# testbrd.net
KiCad netlist of a schematic drawn in EAGLE
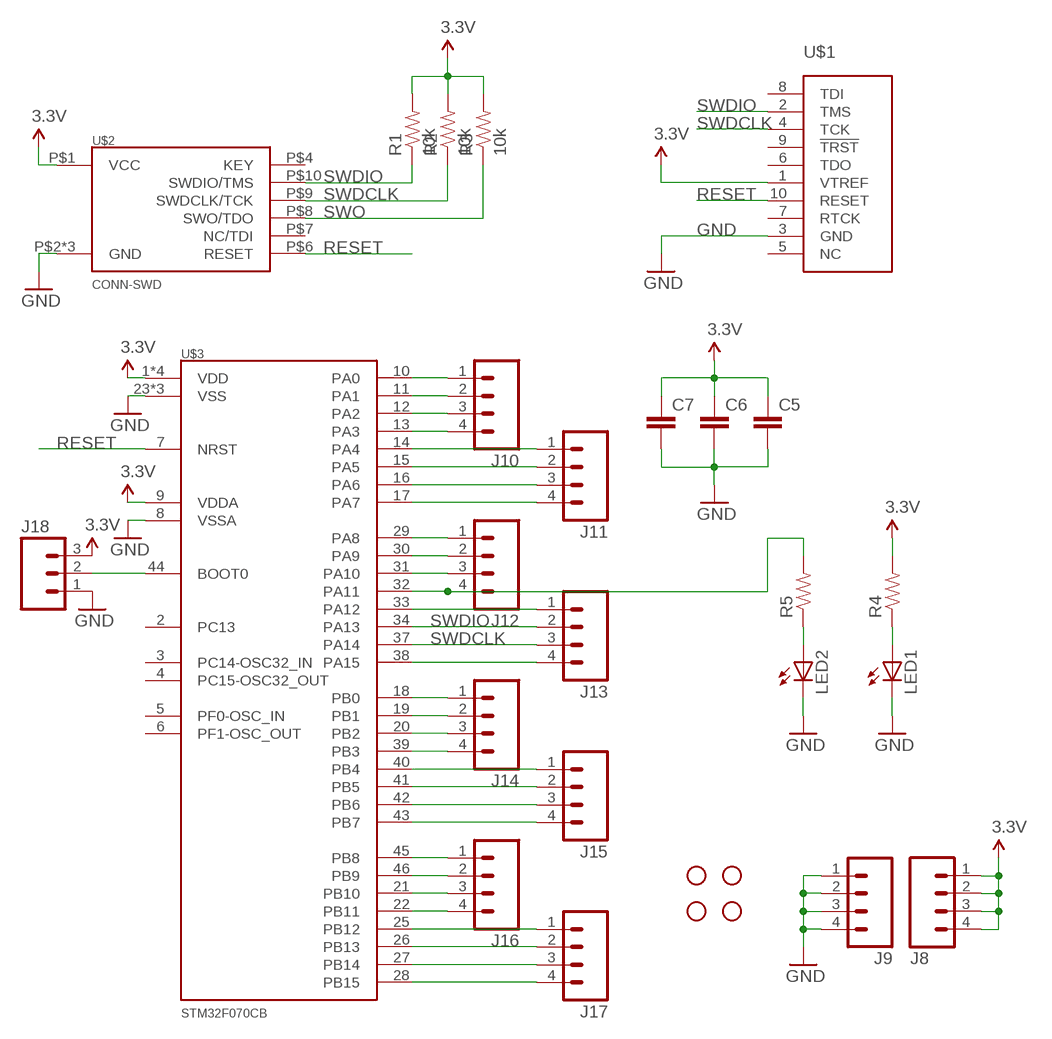
[diagram p0: schematic, sheet 1]

(export (version "E")
  (design (tool "Eeschema 10.0.6"))
  (components
    (comp (ref "C5")
      (value "CAP0805")
      (footprint "eagle-import:0805")
      (libsource (lib "eagle-import") (part "CAP0805"))
    )
    (comp (ref "C6")
      (value "CAP0805")
      (footprint "eagle-import:0805")
      (libsource (lib "eagle-import") (part "CAP0805"))
    )
    (comp (ref "C7")
      (value "CAP0805")
      (footprint "eagle-import:0805")
      (libsource (lib "eagle-import") (part "CAP0805"))
    )
    (comp (ref "H1")
      (value "STAND-OFF")
      (footprint "eagle-import:STAND-OFF")
      (libsource (lib "eagle-import") (part "STAND-OFF"))
    )
    (comp (ref "H2")
      (value "STAND-OFF")
      (footprint "eagle-import:STAND-OFF")
      (libsource (lib "eagle-import") (part "STAND-OFF"))
    )
    (comp (ref "H3")
      (value "STAND-OFF")
      (footprint "eagle-import:STAND-OFF")
      (libsource (lib "eagle-import") (part "STAND-OFF"))
    )
    (comp (ref "H4")
      (value "STAND-OFF")
      (footprint "eagle-import:STAND-OFF")
      (libsource (lib "eagle-import") (part "STAND-OFF"))
    )
    (comp (ref "J8")
      (value "M04PTH")
      (footprint "eagle-import:1X04")
      (libsource (lib "eagle-import") (part "M04PTH"))
    )
    (comp (ref "J9")
      (value "M04PTH")
      (footprint "eagle-import:1X04")
      (libsource (lib "eagle-import") (part "M04PTH"))
    )
    (comp (ref "J10")
      (value "M04PTH")
      (footprint "eagle-import:1X04")
      (libsource (lib "eagle-import") (part "M04PTH"))
    )
    (comp (ref "J11")
      (value "M04PTH")
      (footprint "eagle-import:1X04")
      (libsource (lib "eagle-import") (part "M04PTH"))
    )
    (comp (ref "J12")
      (value "M04PTH")
      (footprint "eagle-import:1X04")
      (libsource (lib "eagle-import") (part "M04PTH"))
    )
    (comp (ref "J13")
      (value "M04PTH")
      (footprint "eagle-import:1X04")
      (libsource (lib "eagle-import") (part "M04PTH"))
    )
    (comp (ref "J14")
      (value "M04PTH")
      (footprint "eagle-import:1X04")
      (libsource (lib "eagle-import") (part "M04PTH"))
    )
    (comp (ref "J15")
      (value "M04PTH")
      (footprint "eagle-import:1X04")
      (libsource (lib "eagle-import") (part "M04PTH"))
    )
    (comp (ref "J16")
      (value "M04PTH")
      (footprint "eagle-import:1X04")
      (libsource (lib "eagle-import") (part "M04PTH"))
    )
    (comp (ref "J17")
      (value "M04PTH")
      (footprint "eagle-import:1X04")
      (libsource (lib "eagle-import") (part "M04PTH"))
    )
    (comp (ref "J18")
      (value "M03PTH")
      (footprint "eagle-import:1X03")
      (libsource (lib "eagle-import") (part "M03PTH"))
    )
    (comp (ref "LED1")
      (value "LEDCHIPLED_0805")
      (footprint "eagle-import:CHIPLED_0805")
      (libsource (lib "eagle-import") (part "LEDCHIPLED_0805"))
    )
    (comp (ref "LED2")
      (value "LEDCHIPLED_0805")
      (footprint "eagle-import:CHIPLED_0805")
      (libsource (lib "eagle-import") (part "LEDCHIPLED_0805"))
    )
    (comp (ref "R1")
      (value "10k")
      (footprint "eagle-import:0805")
      (libsource (lib "eagle-import") (part "RESISTOR0805-RES"))
    )
    (comp (ref "R2")
      (value "10k")
      (footprint "eagle-import:0805")
      (libsource (lib "eagle-import") (part "RESISTOR0805-RES"))
    )
    (comp (ref "R3")
      (value "10k")
      (footprint "eagle-import:0805")
      (libsource (lib "eagle-import") (part "RESISTOR0805-RES"))
    )
    (comp (ref "R4")
      (value "RESISTOR0805-RES")
      (footprint "eagle-import:0805")
      (libsource (lib "eagle-import") (part "RESISTOR0805-RES"))
    )
    (comp (ref "R5")
      (value "RESISTOR0805-RES")
      (footprint "eagle-import:0805")
      (libsource (lib "eagle-import") (part "RESISTOR0805-RES"))
    )
    (comp (ref "U$1")
      (value "TC2050-MCP-NL")
      (footprint "eagle-import:TC2050")
      (libsource (lib "eagle-import") (part "TC2050-MCP-NL"))
    )
    (comp (ref "U$2")
      (value "CONN-SWD")
      (footprint "eagle-import:CONN2X5")
      (libsource (lib "eagle-import") (part "CONN-SWD"))
    )
    (comp (ref "U$3")
      (value "STM32F070CB")
      (footprint "eagle-import:LQFP-48")
      (libsource (lib "eagle-import") (part "STM32F070CB"))
    )
  )
  (nets
    (net (code "1") (name "/RESET") (class "Default")
      (node (ref "U$1") (pin "10") (pinfunction "RESET_10") (pintype "bidirectional"))
      (node (ref "U$2") (pin "P$6") (pinfunction "RESET_P$6") (pintype "bidirectional"))
      (node (ref "U$3") (pin "7") (pinfunction "NRST_7") (pintype "bidirectional"))
    )
    (net (code "2") (name "/SWDCLK") (class "Default")
      (node (ref "J13") (pin "3") (pinfunction "3_3") (pintype "passive"))
      (node (ref "R2") (pin "1") (pinfunction "1_1") (pintype "passive"))
      (node (ref "U$1") (pin "4") (pinfunction "TCK_4") (pintype "bidirectional"))
      (node (ref "U$2") (pin "P$9") (pinfunction "SWDCLK/TCK_P$9") (pintype "bidirectional"))
      (node (ref "U$3") (pin "37") (pinfunction "PA14_37") (pintype "bidirectional"))
    )
    (net (code "3") (name "/SWDIO") (class "Default")
      (node (ref "J13") (pin "2") (pinfunction "2_2") (pintype "passive"))
      (node (ref "R1") (pin "1") (pinfunction "1_1") (pintype "passive"))
      (node (ref "U$1") (pin "2") (pinfunction "TMS_2") (pintype "bidirectional"))
      (node (ref "U$2") (pin "P$10") (pinfunction "SWDIO/TMS_P$10") (pintype "bidirectional"))
      (node (ref "U$3") (pin "34") (pinfunction "PA13_34") (pintype "bidirectional"))
    )
    (net (code "4") (name "/SWO") (class "Default")
      (node (ref "R3") (pin "1") (pinfunction "1_1") (pintype "passive"))
      (node (ref "U$2") (pin "P$8") (pinfunction "SWO/TDO_P$8") (pintype "bidirectional"))
    )
    (net (code "5") (name "3.3V") (class "Default")
      (node (ref "C5") (pin "1") (pinfunction "1_1") (pintype "passive"))
      (node (ref "C6") (pin "1") (pinfunction "1_1") (pintype "passive"))
      (node (ref "C7") (pin "1") (pinfunction "1_1") (pintype "passive"))
      (node (ref "J18") (pin "3") (pinfunction "3_3") (pintype "passive"))
      (node (ref "J8") (pin "1") (pinfunction "1_1") (pintype "passive"))
      (node (ref "J8") (pin "2") (pinfunction "2_2") (pintype "passive"))
      (node (ref "J8") (pin "3") (pinfunction "3_3") (pintype "passive"))
      (node (ref "J8") (pin "4") (pinfunction "4_4") (pintype "passive"))
      (node (ref "R1") (pin "2") (pinfunction "2_2") (pintype "passive"))
      (node (ref "R2") (pin "2") (pinfunction "2_2") (pintype "passive"))
      (node (ref "R3") (pin "2") (pinfunction "2_2") (pintype "passive"))
      (node (ref "R4") (pin "2") (pinfunction "2_2") (pintype "passive"))
      (node (ref "U$1") (pin "1") (pinfunction "VTREF_1") (pintype "bidirectional"))
      (node (ref "U$2") (pin "P$1") (pinfunction "VCC_P$1") (pintype "bidirectional"))
      (node (ref "U$3") (pin "1") (pinfunction "VDD_1") (pintype "bidirectional"))
      (node (ref "U$3") (pin "24") (pinfunction "VDD_24") (pintype "bidirectional"))
      (node (ref "U$3") (pin "36") (pinfunction "VDD_36") (pintype "bidirectional"))
      (node (ref "U$3") (pin "48") (pinfunction "VDD_48") (pintype "bidirectional"))
      (node (ref "U$3") (pin "9") (pinfunction "VDDA_9") (pintype "bidirectional"))
    )
    (net (code "6") (name "GND") (class "Default")
      (node (ref "C5") (pin "2") (pinfunction "2_2") (pintype "passive"))
      (node (ref "C6") (pin "2") (pinfunction "2_2") (pintype "passive"))
      (node (ref "C7") (pin "2") (pinfunction "2_2") (pintype "passive"))
      (node (ref "J18") (pin "1") (pinfunction "1_1") (pintype "passive"))
      (node (ref "J9") (pin "1") (pinfunction "1_1") (pintype "passive"))
      (node (ref "J9") (pin "2") (pinfunction "2_2") (pintype "passive"))
      (node (ref "J9") (pin "3") (pinfunction "3_3") (pintype "passive"))
      (node (ref "J9") (pin "4") (pinfunction "4_4") (pintype "passive"))
      (node (ref "LED1") (pin "C") (pinfunction "C_C") (pintype "passive"))
      (node (ref "LED2") (pin "C") (pinfunction "C_C") (pintype "passive"))
      (node (ref "U$1") (pin "3") (pinfunction "GND_3") (pintype "bidirectional"))
      (node (ref "U$2") (pin "P$2") (pinfunction "GND_P$2") (pintype "bidirectional"))
      (node (ref "U$2") (pin "P$3") (pinfunction "GND_P$3") (pintype "bidirectional"))
      (node (ref "U$2") (pin "P$5") (pinfunction "GND_P$5") (pintype "bidirectional"))
      (node (ref "U$3") (pin "23") (pinfunction "VSS_23") (pintype "bidirectional"))
      (node (ref "U$3") (pin "35") (pinfunction "VSS_35") (pintype "bidirectional"))
      (node (ref "U$3") (pin "47") (pinfunction "VSS_47") (pintype "bidirectional"))
      (node (ref "U$3") (pin "8") (pinfunction "VSSA_8") (pintype "bidirectional"))
    )
    (net (code "7") (name "Net-(LED1-PadA)") (class "Default")
      (node (ref "LED1") (pin "A") (pinfunction "A_A") (pintype "passive"))
      (node (ref "R4") (pin "1") (pinfunction "1_1") (pintype "passive"))
    )
    (net (code "8") (name "Net-(LED2-PadA)") (class "Default")
      (node (ref "LED2") (pin "A") (pinfunction "A_A") (pintype "passive"))
      (node (ref "R5") (pin "1") (pinfunction "1_1") (pintype "passive"))
    )
    (net (code "9") (name "Net-(U$3-BOOT0)") (class "Default")
      (node (ref "J18") (pin "2") (pinfunction "2_2") (pintype "passive"))
      (node (ref "U$3") (pin "44") (pinfunction "BOOT0_44") (pintype "bidirectional"))
    )
    (net (code "10") (name "Net-(U$3-PA0)") (class "Default")
      (node (ref "J10") (pin "1") (pinfunction "1_1") (pintype "passive"))
      (node (ref "U$3") (pin "10") (pinfunction "PA0_10") (pintype "bidirectional"))
    )
    (net (code "11") (name "Net-(U$3-PA1)") (class "Default")
      (node (ref "J10") (pin "2") (pinfunction "2_2") (pintype "passive"))
      (node (ref "U$3") (pin "11") (pinfunction "PA1_11") (pintype "bidirectional"))
    )
    (net (code "12") (name "Net-(U$3-PA2)") (class "Default")
      (node (ref "J10") (pin "3") (pinfunction "3_3") (pintype "passive"))
      (node (ref "U$3") (pin "12") (pinfunction "PA2_12") (pintype "bidirectional"))
    )
    (net (code "13") (name "Net-(U$3-PA3)") (class "Default")
      (node (ref "J10") (pin "4") (pinfunction "4_4") (pintype "passive"))
      (node (ref "U$3") (pin "13") (pinfunction "PA3_13") (pintype "bidirectional"))
    )
    (net (code "14") (name "Net-(U$3-PA4)") (class "Default")
      (node (ref "J11") (pin "1") (pinfunction "1_1") (pintype "passive"))
      (node (ref "U$3") (pin "14") (pinfunction "PA4_14") (pintype "bidirectional"))
    )
    (net (code "15") (name "Net-(U$3-PA5)") (class "Default")
      (node (ref "J11") (pin "2") (pinfunction "2_2") (pintype "passive"))
      (node (ref "U$3") (pin "15") (pinfunction "PA5_15") (pintype "bidirectional"))
    )
    (net (code "16") (name "Net-(U$3-PA6)") (class "Default")
      (node (ref "J11") (pin "3") (pinfunction "3_3") (pintype "passive"))
      (node (ref "U$3") (pin "16") (pinfunction "PA6_16") (pintype "bidirectional"))
    )
    (net (code "17") (name "Net-(U$3-PA7)") (class "Default")
      (node (ref "J11") (pin "4") (pinfunction "4_4") (pintype "passive"))
      (node (ref "U$3") (pin "17") (pinfunction "PA7_17") (pintype "bidirectional"))
    )
    (net (code "18") (name "Net-(U$3-PA8)") (class "Default")
      (node (ref "J12") (pin "1") (pinfunction "1_1") (pintype "passive"))
      (node (ref "U$3") (pin "29") (pinfunction "PA8_29") (pintype "bidirectional"))
    )
    (net (code "19") (name "Net-(U$3-PA9)") (class "Default")
      (node (ref "J12") (pin "2") (pinfunction "2_2") (pintype "passive"))
      (node (ref "U$3") (pin "30") (pinfunction "PA9_30") (pintype "bidirectional"))
    )
    (net (code "20") (name "Net-(U$3-PA10)") (class "Default")
      (node (ref "J12") (pin "3") (pinfunction "3_3") (pintype "passive"))
      (node (ref "U$3") (pin "31") (pinfunction "PA10_31") (pintype "bidirectional"))
    )
    (net (code "21") (name "Net-(U$3-PA11)") (class "Default")
      (node (ref "J12") (pin "4") (pinfunction "4_4") (pintype "passive"))
      (node (ref "R5") (pin "2") (pinfunction "2_2") (pintype "passive"))
      (node (ref "U$3") (pin "32") (pinfunction "PA11_32") (pintype "bidirectional"))
    )
    (net (code "22") (name "Net-(U$3-PA12)") (class "Default")
      (node (ref "J13") (pin "1") (pinfunction "1_1") (pintype "passive"))
      (node (ref "U$3") (pin "33") (pinfunction "PA12_33") (pintype "bidirectional"))
    )
    (net (code "23") (name "Net-(U$3-PA15)") (class "Default")
      (node (ref "J13") (pin "4") (pinfunction "4_4") (pintype "passive"))
      (node (ref "U$3") (pin "38") (pinfunction "PA15_38") (pintype "bidirectional"))
    )
    (net (code "24") (name "Net-(U$3-PB0)") (class "Default")
      (node (ref "J14") (pin "1") (pinfunction "1_1") (pintype "passive"))
      (node (ref "U$3") (pin "18") (pinfunction "PB0_18") (pintype "bidirectional"))
    )
    (net (code "25") (name "Net-(U$3-PB1)") (class "Default")
      (node (ref "J14") (pin "2") (pinfunction "2_2") (pintype "passive"))
      (node (ref "U$3") (pin "19") (pinfunction "PB1_19") (pintype "bidirectional"))
    )
    (net (code "26") (name "Net-(U$3-PB2)") (class "Default")
      (node (ref "J14") (pin "3") (pinfunction "3_3") (pintype "passive"))
      (node (ref "U$3") (pin "20") (pinfunction "PB2_20") (pintype "bidirectional"))
    )
    (net (code "27") (name "Net-(U$3-PB3)") (class "Default")
      (node (ref "J14") (pin "4") (pinfunction "4_4") (pintype "passive"))
      (node (ref "U$3") (pin "39") (pinfunction "PB3_39") (pintype "bidirectional"))
    )
    (net (code "28") (name "Net-(U$3-PB4)") (class "Default")
      (node (ref "J15") (pin "1") (pinfunction "1_1") (pintype "passive"))
      (node (ref "U$3") (pin "40") (pinfunction "PB4_40") (pintype "bidirectional"))
    )
    (net (code "29") (name "Net-(U$3-PB5)") (class "Default")
      (node (ref "J15") (pin "2") (pinfunction "2_2") (pintype "passive"))
      (node (ref "U$3") (pin "41") (pinfunction "PB5_41") (pintype "bidirectional"))
    )
    (net (code "30") (name "Net-(U$3-PB6)") (class "Default")
      (node (ref "J15") (pin "3") (pinfunction "3_3") (pintype "passive"))
      (node (ref "U$3") (pin "42") (pinfunction "PB6_42") (pintype "bidirectional"))
    )
    (net (code "31") (name "Net-(U$3-PB7)") (class "Default")
      (node (ref "J15") (pin "4") (pinfunction "4_4") (pintype "passive"))
      (node (ref "U$3") (pin "43") (pinfunction "PB7_43") (pintype "bidirectional"))
    )
    (net (code "32") (name "Net-(U$3-PB8)") (class "Default")
      (node (ref "J16") (pin "1") (pinfunction "1_1") (pintype "passive"))
      (node (ref "U$3") (pin "45") (pinfunction "PB8_45") (pintype "bidirectional"))
    )
    (net (code "33") (name "Net-(U$3-PB9)") (class "Default")
      (node (ref "J16") (pin "2") (pinfunction "2_2") (pintype "passive"))
      (node (ref "U$3") (pin "46") (pinfunction "PB9_46") (pintype "bidirectional"))
    )
    (net (code "34") (name "Net-(U$3-PB10)") (class "Default")
      (node (ref "J16") (pin "3") (pinfunction "3_3") (pintype "passive"))
      (node (ref "U$3") (pin "21") (pinfunction "PB10_21") (pintype "bidirectional"))
    )
    (net (code "35") (name "Net-(U$3-PB11)") (class "Default")
      (node (ref "J16") (pin "4") (pinfunction "4_4") (pintype "passive"))
      (node (ref "U$3") (pin "22") (pinfunction "PB11_22") (pintype "bidirectional"))
    )
    (net (code "36") (name "Net-(U$3-PB12)") (class "Default")
      (node (ref "J17") (pin "1") (pinfunction "1_1") (pintype "passive"))
      (node (ref "U$3") (pin "25") (pinfunction "PB12_25") (pintype "bidirectional"))
    )
    (net (code "37") (name "Net-(U$3-PB13)") (class "Default")
      (node (ref "J17") (pin "2") (pinfunction "2_2") (pintype "passive"))
      (node (ref "U$3") (pin "26") (pinfunction "PB13_26") (pintype "bidirectional"))
    )
    (net (code "38") (name "Net-(U$3-PB14)") (class "Default")
      (node (ref "J17") (pin "3") (pinfunction "3_3") (pintype "passive"))
      (node (ref "U$3") (pin "27") (pinfunction "PB14_27") (pintype "bidirectional"))
    )
    (net (code "39") (name "Net-(U$3-PB15)") (class "Default")
      (node (ref "J17") (pin "4") (pinfunction "4_4") (pintype "passive"))
      (node (ref "U$3") (pin "28") (pinfunction "PB15_28") (pintype "bidirectional"))
    )
    (net (code "40") (name "unconnected-(U$1-NC-Pad5)") (class "Default")
      (node (ref "U$1") (pin "5") (pinfunction "NC_5") (pintype "bidirectional"))
    )
    (net (code "41") (name "unconnected-(U$1-RTCK-Pad7)") (class "Default")
      (node (ref "U$1") (pin "7") (pinfunction "RTCK_7") (pintype "bidirectional"))
    )
    (net (code "42") (name "unconnected-(U$1-TDI-Pad8)") (class "Default")
      (node (ref "U$1") (pin "8") (pinfunction "TDI_8") (pintype "bidirectional"))
    )
    (net (code "43") (name "unconnected-(U$1-TDO-Pad6)") (class "Default")
      (node (ref "U$1") (pin "6") (pinfunction "TDO_6") (pintype "bidirectional"))
    )
    (net (code "44") (name "unconnected-(U$1-~{TRST}-Pad9)") (class "Default")
      (node (ref "U$1") (pin "9") (pinfunction "~{TRST}_9") (pintype "bidirectional"))
    )
    (net (code "45") (name "unconnected-(U$2-KEY-PadP$4)") (class "Default")
      (node (ref "U$2") (pin "P$4") (pinfunction "KEY_P$4") (pintype "bidirectional"))
    )
    (net (code "46") (name "unconnected-(U$2-NC{slash}TDI-PadP$7)") (class "Default")
      (node (ref "U$2") (pin "P$7") (pinfunction "NC/TDI_P$7") (pintype "bidirectional"))
    )
    (net (code "47") (name "unconnected-(U$3-PC13-Pad2)") (class "Default")
      (node (ref "U$3") (pin "2") (pinfunction "PC13_2") (pintype "bidirectional"))
    )
    (net (code "48") (name "unconnected-(U$3-PC14-OSC32_IN-Pad3)") (class "Default")
      (node (ref "U$3") (pin "3") (pinfunction "PC14-OSC32_IN_3") (pintype "bidirectional"))
    )
    (net (code "49") (name "unconnected-(U$3-PC15-OSC32_OUT-Pad4)") (class "Default")
      (node (ref "U$3") (pin "4") (pinfunction "PC15-OSC32_OUT_4") (pintype "bidirectional"))
    )
    (net (code "50") (name "unconnected-(U$3-PF0-OSC_IN-Pad5)") (class "Default")
      (node (ref "U$3") (pin "5") (pinfunction "PF0-OSC_IN_5") (pintype "bidirectional"))
    )
    (net (code "51") (name "unconnected-(U$3-PF1-OSC_OUT-Pad6)") (class "Default")
      (node (ref "U$3") (pin "6") (pinfunction "PF1-OSC_OUT_6") (pintype "bidirectional"))
    )
  )
)
